# SCH_NFC-BOARD_2026-05-23.net
KiCad netlist of a schematic drawn in EasyEDA
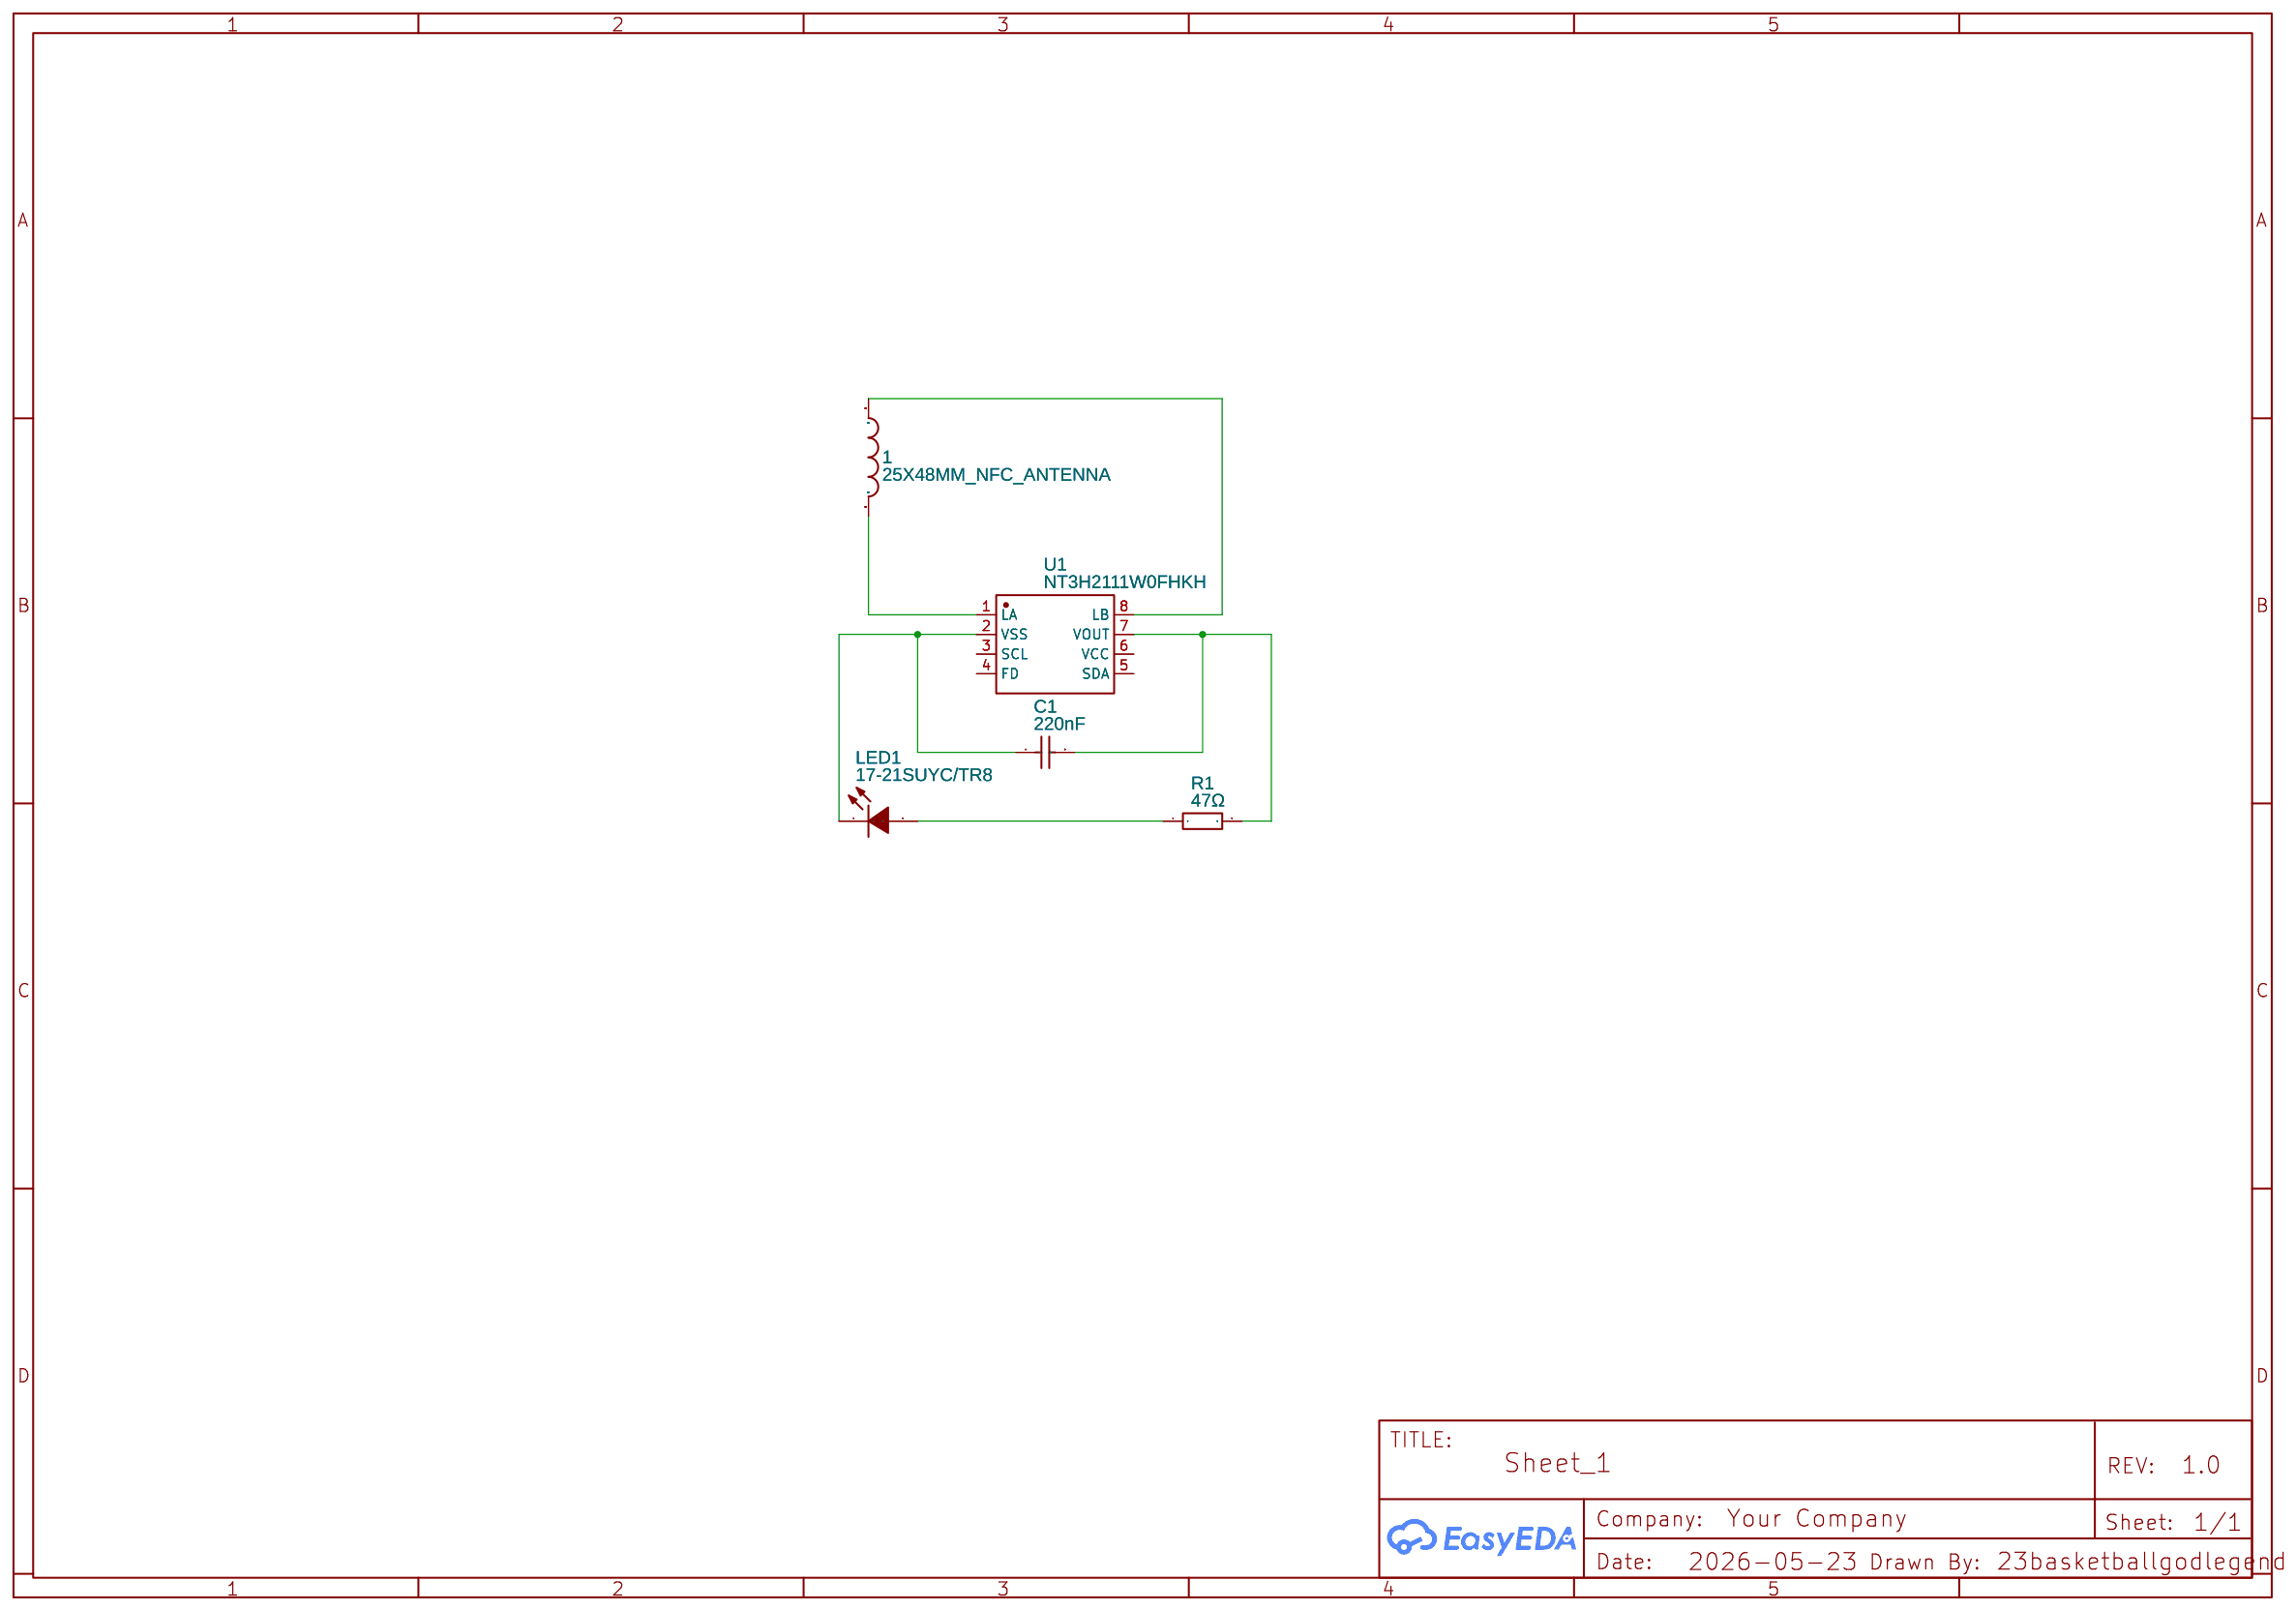
[diagram p0: schematic sheet]

(export (version "E")
  (design (tool "Eeschema 10.0.6"))
  (components
    (comp (ref "1") (value "25X48MM_NFC_ANTENNA") (libsource (lib "") (part "25X48MM_NFC_ANTENNA")))
    (comp (ref "C1")
      (value "220nF")
      (fields
        (field (name "Manufacturer Part") "CL10B224KA8NNNC")
        (field (name "Manufacturer") "SAMSUNG(三星)")
      )
      (libsource (lib "") (part "CL10B224KA8NNNC"))
    )
    (comp (ref "LED1")
      (value "17-21SUYC/TR8")
      (fields (field (name "Manufacturer Part") "KT-0805黄灯") (field (name "Manufacturer") "KENTO"))
      (libsource (lib "") (part "17-21SUYC/TR8"))
    )
    (comp (ref "R1")
      (value "47Ω")
      (fields
        (field (name "Manufacturer Part") "0603WAF470JT5E")
        (field (name "Manufacturer") "UNI-ROYAL(厚声)")
      )
      (libsource (lib "") (part "0603WAF470JT5E"))
    )
    (comp (ref "U1")
      (value "NT3H2111W0FHKH")
      (fields (field (name "Manufacturer") "NXP(恩智浦)"))
      (libsource (lib "") (part "NT3H2111W0FHKH"))
    )
  )
  (nets
    (net (code "1") (name "Net-(LED1-+)") (class "Default")
      (node (ref "LED1") (pin "1") (pinfunction "+_1") (pintype "unspecified"))
      (node (ref "R1") (pin "1") (pinfunction "1_1") (pintype "input"))
    )
    (net (code "2") (name "Net-(LED1--)") (class "Default")
      (node (ref "C1") (pin "1") (pinfunction "1_1") (pintype "input"))
      (node (ref "LED1") (pin "2") (pinfunction "-_2") (pintype "unspecified"))
      (node (ref "U1") (pin "2") (pinfunction "VSS_2") (pintype "unspecified"))
    )
    (net (code "3") (name "Net-(U1-LA)") (class "Default")
      (node (ref "1") (pin "P$2") (pinfunction "P$2_P$2") (pintype "bidirectional"))
      (node (ref "U1") (pin "1") (pinfunction "LA_1") (pintype "unspecified"))
    )
    (net (code "4") (name "Net-(U1-LB)") (class "Default")
      (node (ref "1") (pin "P$1") (pinfunction "P$1_P$1") (pintype "bidirectional"))
      (node (ref "U1") (pin "8") (pinfunction "LB_8") (pintype "unspecified"))
    )
    (net (code "5") (name "Net-(U1-VOUT)") (class "Default")
      (node (ref "C1") (pin "2") (pinfunction "2_2") (pintype "input"))
      (node (ref "R1") (pin "2") (pinfunction "2_2") (pintype "input"))
      (node (ref "U1") (pin "7") (pinfunction "VOUT_7") (pintype "unspecified"))
    )
    (net (code "6") (name "unconnected-(U1-FD-Pad4)") (class "Default")
      (node (ref "U1") (pin "4") (pinfunction "FD_4") (pintype "unspecified"))
    )
    (net (code "7") (name "unconnected-(U1-SCL-Pad3)") (class "Default")
      (node (ref "U1") (pin "3") (pinfunction "SCL_3") (pintype "unspecified"))
    )
    (net (code "8") (name "unconnected-(U1-SDA-Pad5)") (class "Default")
      (node (ref "U1") (pin "5") (pinfunction "SDA_5") (pintype "unspecified"))
    )
    (net (code "9") (name "unconnected-(U1-VCC-Pad6)") (class "Default")
      (node (ref "U1") (pin "6") (pinfunction "VCC_6") (pintype "unspecified"))
    )
  )
)
